# energy.net
KiCad netlist of a schematic drawn in Altium Designer
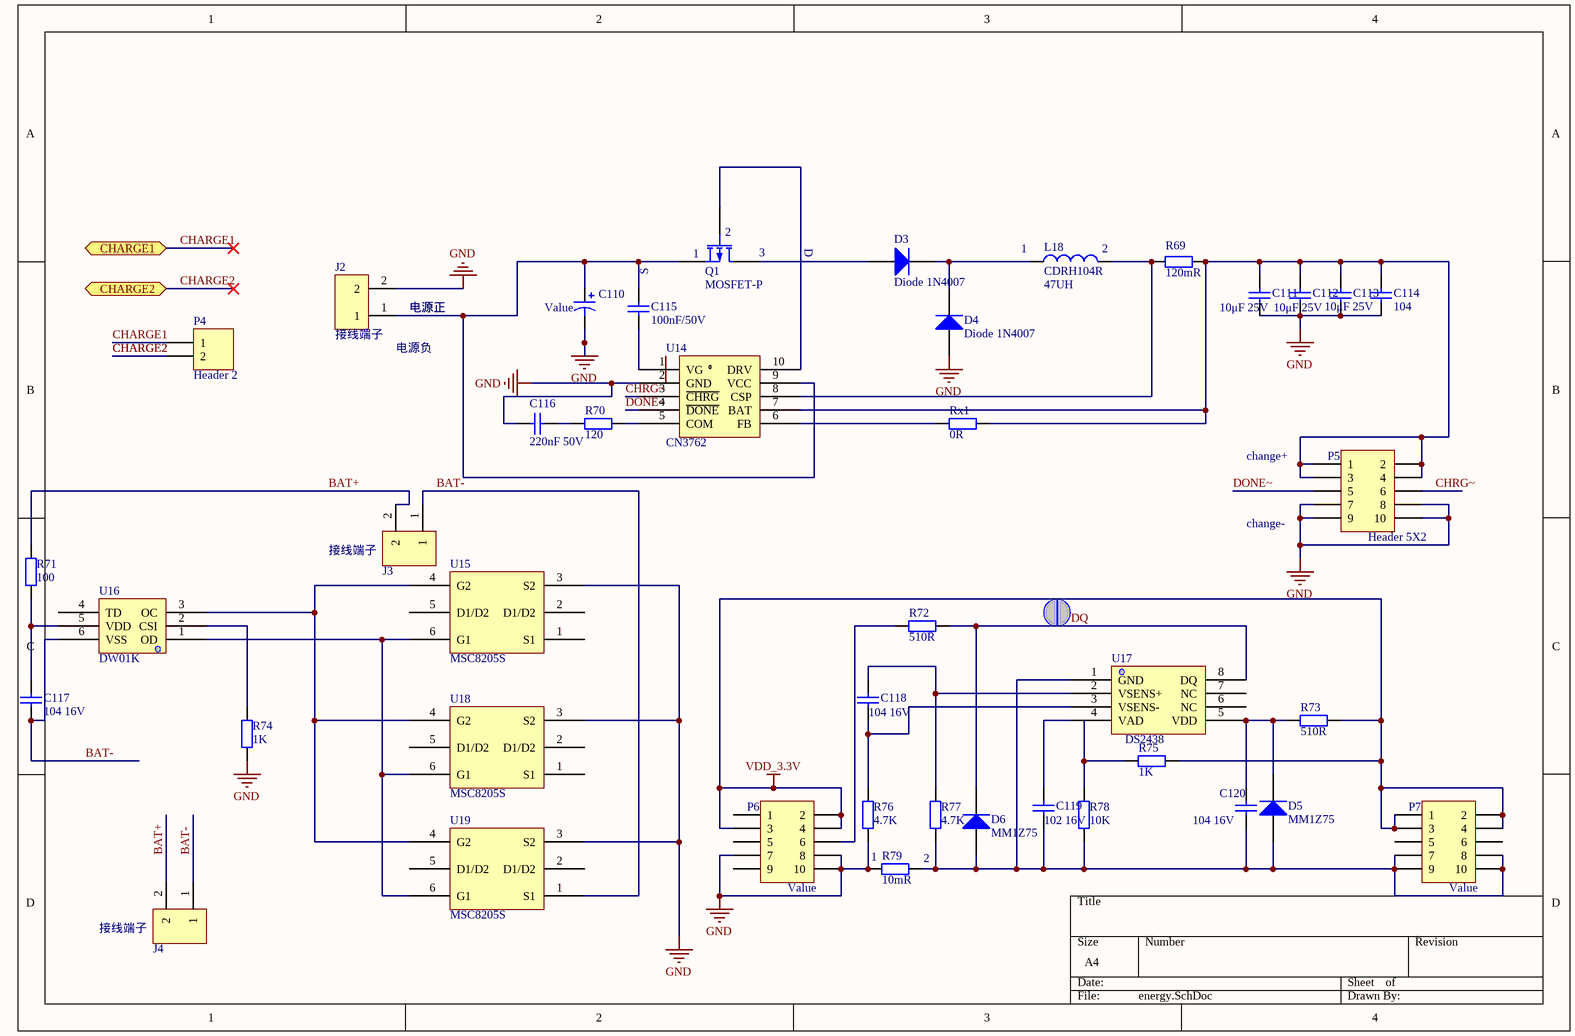
[diagram p0: energy.SchDoc]

(export (version "E")
  (design (tool "Eeschema 10.0.6"))
  (components
    (comp (ref "C110") (value "Value") (footprint "RB5.0-13") (libsource (lib "Spartan") (part "Cap_Pol")))
    (comp (ref "C111") (value "10μF 25V") (footprint "0805C") (libsource (lib "Spartan") (part "Cap")))
    (comp (ref "C112") (value "10μF 25V") (footprint "0805C") (libsource (lib "Spartan") (part "Cap")))
    (comp (ref "C113") (value "10μF 25V") (footprint "0805C") (libsource (lib "Spartan") (part "Cap")))
    (comp (ref "C114") (value "104") (footprint "0805C") (libsource (lib "Spartan") (part "Cap")))
    (comp (ref "C115") (value "100nF/50V") (footprint "0805C") (libsource (lib "Spartan") (part "Cap")))
    (comp (ref "C116") (value "220nF 50V") (footprint "0805C") (libsource (lib "Spartan") (part "Cap")))
    (comp (ref "C117") (value "104 16V") (footprint "0805C") (libsource (lib "PulsePower-Buck") (part "Cap")))
    (comp (ref "C118") (value "104 16V") (footprint "0805C") (libsource (lib "Spartan") (part "Cap")))
    (comp (ref "C119") (value "102 16V") (footprint "0805C") (libsource (lib "Spartan") (part "Cap")))
    (comp (ref "C120") (value "104 16V") (footprint "0805C") (libsource (lib "Spartan") (part "Cap")))
    (comp (ref "D3")
      (value "Diode 1N4007")
      (footprint "DO-41")
      (description "1 Amp General Purpose Rectifier")
      (fields (field (name "PUBLISHER") "Altium Limited"))
      (libsource (lib "Miscellaneous Devices") (part "Diode 1N4007"))
    )
    (comp (ref "D4")
      (value "Diode 1N4007")
      (footprint "DO-41")
      (description "1 Amp General Purpose Rectifier")
      (fields (field (name "PUBLISHER") "Altium Limited"))
      (libsource (lib "Miscellaneous Devices") (part "Diode 1N4007"))
    )
    (comp (ref "D5")
      (value "MM1Z75")
      (footprint "DO-41")
      (description "1 Amp General Purpose Rectifier")
      (fields (field (name "PUBLISHER") "Altium Limited"))
      (libsource (lib "Miscellaneous Devices") (part "Diode 1N4007"))
    )
    (comp (ref "D6")
      (value "MM1Z75")
      (footprint "DO-41")
      (description "1 Amp General Purpose Rectifier")
      (fields (field (name "PUBLISHER") "Altium Limited"))
      (libsource (lib "Miscellaneous Devices") (part "Diode 1N4007"))
    )
    (comp (ref "J2")
      (value "接线端子")
      (footprint "接线端子KF301-2P")
      (fields
        (field (name "原理图绘制者") "刘永钦")
        (field (name "原理图提供者") "刘永钦")
        (field (name "原理图审核人1") "徐鹏飞")
        (field (name "封装接线端子KF301-2P绘制者") "10级718学长")
        (field (name "封装接线端子KF301-2P提供者") "刘永钦")
        (field (name "封装接线端子KF301-2P审核人1") "徐鹏飞")
        (field (name "原理图审核人2") "朱觉文")
        (field (name "封装接线端子KF301-2P审核人2") "朱觉文")
      )
      (libsource (lib "") (part "接线端子_1"))
    )
    (comp (ref "J3")
      (value "接线端子")
      (footprint "接线端子KF301-2P")
      (fields
        (field (name "原理图绘制者") "刘永钦")
        (field (name "原理图提供者") "刘永钦")
        (field (name "原理图审核人1") "徐鹏飞")
        (field (name "封装接线端子KF301-2P绘制者") "10级718学长")
        (field (name "封装接线端子KF301-2P提供者") "刘永钦")
        (field (name "封装接线端子KF301-2P审核人1") "徐鹏飞")
        (field (name "原理图审核人2") "朱觉文")
        (field (name "封装接线端子KF301-2P审核人2") "朱觉文")
      )
      (libsource (lib "Dugu") (part "接线端子"))
    )
    (comp (ref "J4")
      (value "接线端子")
      (footprint "接线端子KF301-2P")
      (fields
        (field (name "原理图绘制者") "刘永钦")
        (field (name "原理图提供者") "刘永钦")
        (field (name "原理图审核人1") "徐鹏飞")
        (field (name "封装接线端子KF301-2P绘制者") "10级718学长")
        (field (name "封装接线端子KF301-2P提供者") "刘永钦")
        (field (name "封装接线端子KF301-2P审核人1") "徐鹏飞")
        (field (name "原理图审核人2") "朱觉文")
        (field (name "封装接线端子KF301-2P审核人2") "朱觉文")
      )
      (libsource (lib "Dugu") (part "接线端子"))
    )
    (comp (ref "L18")
      (value "CDRH104R")
      (footprint "0402-A")
      (description "Inductor")
      (fields (field (name "ALTIUM_VALUE") "47UH") (field (name "PUBLISHER") "Altium Limited"))
      (libsource (lib "Miscellaneous Devices") (part "Inductor"))
    )
    (comp (ref "P4")
      (value "Header 2")
      (footprint "HDR1X2")
      (description "Header, 2-Pin")
      (fields (field (name "PUBLISHER") "Altium Limited"))
      (libsource (lib "Miscellaneous Connectors") (part "Header 2"))
    )
    (comp (ref "P5")
      (value "Header 5X2")
      (footprint "HDR2X5")
      (description "Header, 5-Pin, Dual row")
      (fields (field (name "PUBLISHER") "Altium Limited"))
      (libsource (lib "Miscellaneous Connectors") (part "Header 5X2"))
    )
    (comp (ref "P6")
      (value "Value")
      (footprint "HDR2X5")
      (description "Header, 5-Pin, Dual row")
      (fields (field (name "PUBLISHER") "Altium Limited"))
      (libsource (lib "Miscellaneous Connectors") (part "Header 5X2"))
    )
    (comp (ref "P7")
      (value "Value")
      (footprint "HDR2X5")
      (description "Header, 5-Pin, Dual row")
      (fields (field (name "PUBLISHER") "Altium Limited"))
      (libsource (lib "Miscellaneous Connectors") (part "Header 5X2"))
    )
    (comp (ref "Q1")
      (value "MOSFET-P")
      (footprint "E3")
      (description "P-Channel MOSFET")
      (fields (field (name "PUBLISHER") "Altium Limited"))
      (libsource (lib "Miscellaneous Devices") (part "MOSFET-P"))
    )
    (comp (ref "R69") (value "120mR") (footprint "0805R") (libsource (lib "") (part "Res_2")))
    (comp (ref "R70") (value "120") (footprint "0805R") (libsource (lib "") (part "Res_2")))
    (comp (ref "R71") (value "100") (footprint "0805R") (libsource (lib "") (part "Res_1")))
    (comp (ref "R72") (value "510R") (footprint "0805R") (libsource (lib "") (part "Res_2")))
    (comp (ref "R73") (value "510R") (footprint "0805R") (libsource (lib "") (part "Res_2")))
    (comp (ref "R74") (value "1K") (footprint "0805R") (libsource (lib "") (part "Res_1")))
    (comp (ref "R75") (value "1K") (footprint "0805R") (libsource (lib "") (part "Res_2")))
    (comp (ref "R76") (value "4.7K") (footprint "0805R") (libsource (lib "") (part "Res_3")))
    (comp (ref "R77") (value "4.7K") (footprint "0805R") (libsource (lib "") (part "Res_3")))
    (comp (ref "R78") (value "10K") (footprint "0805R") (libsource (lib "") (part "Res_3")))
    (comp (ref "R79") (value "10mR") (footprint "0805R") (libsource (lib "Spartan") (part "Res")))
    (comp (ref "Rx1") (value "0R") (footprint "0805R") (libsource (lib "") (part "Res_2")))
    (comp (ref "U14")
      (value "CN3762")
      (footprint "SOP100P600X175-10N")
      (libsource (lib "EnergyChips") (part "CN3762"))
    )
    (comp (ref "U15")
      (value "MSC8205S")
      (footprint "SOT95P290X124-6N")
      (libsource (lib "EnergyChips") (part "MSC8205S"))
    )
    (comp (ref "U16")
      (value "DW01K")
      (footprint "SOT95P280X125-6N")
      (libsource (lib "EnergyChips") (part "DW01K"))
    )
    (comp (ref "U17")
      (value "DS2438")
      (footprint "SOP127P800X216-8N")
      (libsource (lib "EnergyChips") (part "DS2438"))
    )
    (comp (ref "U18")
      (value "MSC8205S")
      (footprint "SOT95P290X124-6N")
      (libsource (lib "EnergyChips") (part "MSC8205S"))
    )
    (comp (ref "U19")
      (value "MSC8205S")
      (footprint "SOT95P290X124-6N")
      (libsource (lib "EnergyChips") (part "MSC8205S"))
    )
  )
  (nets
    (net (code "1") (name "/BAT+") (class "Default")
      (node (ref "J3") (pin "2") (pinfunction "2_2") (pintype "power_in"))
      (node (ref "J4") (pin "2") (pinfunction "2_2") (pintype "power_in"))
      (node (ref "R71") (pin "2") (pinfunction "2_2") (pintype "passive"))
    )
    (net (code "2") (name "/BAT-") (class "Default")
      (node (ref "C117") (pin "1") (pinfunction "1_1") (pintype "passive"))
      (node (ref "J3") (pin "1") (pinfunction "1_1") (pintype "power_in"))
      (node (ref "J4") (pin "1") (pinfunction "1_1") (pintype "power_in"))
      (node (ref "U16") (pin "6") (pinfunction "VSS_6") (pintype "passive"))
      (node (ref "U19") (pin "1") (pinfunction "S1_1") (pintype "passive"))
    )
    (net (code "3") (name "/CHARGE1") (class "Default")
      (node (ref "P4") (pin "1") (pinfunction "1_1") (pintype "passive+no_connect"))
    )
    (net (code "4") (name "/CHARGE2") (class "Default")
      (node (ref "P4") (pin "2") (pinfunction "2_2") (pintype "passive+no_connect"))
    )
    (net (code "5") (name "/CHRG~") (class "Default")
      (node (ref "P5") (pin "6") (pinfunction "6_6") (pintype "passive"))
      (node (ref "U14") (pin "3") (pinfunction "~{CHRG}_3") (pintype "passive"))
    )
    (net (code "6") (name "/DONE~") (class "Default")
      (node (ref "P5") (pin "5") (pinfunction "5_5") (pintype "passive"))
      (node (ref "U14") (pin "4") (pinfunction "~{DONE}_4") (pintype "passive"))
    )
    (net (code "7") (name "/DQ") (class "Default")
      (node (ref "D6") (pin "2") (pinfunction "K_2") (pintype "passive"))
      (node (ref "R72") (pin "1") (pinfunction "1_1") (pintype "passive"))
      (node (ref "U17") (pin "8") (pinfunction "DQ_8") (pintype "passive"))
    )
    (net (code "8") (name "GND") (class "Default")
      (node (ref "C110") (pin "2") (pinfunction "2_2") (pintype "passive"))
      (node (ref "C111") (pin "2") (pinfunction "2_2") (pintype "passive"))
      (node (ref "C112") (pin "2") (pinfunction "2_2") (pintype "passive"))
      (node (ref "C113") (pin "2") (pinfunction "2_2") (pintype "passive"))
      (node (ref "C114") (pin "2") (pinfunction "2_2") (pintype "passive"))
      (node (ref "C116") (pin "2") (pinfunction "2_2") (pintype "passive"))
      (node (ref "D4") (pin "1") (pinfunction "A_1") (pintype "passive"))
      (node (ref "J2") (pin "2") (pinfunction "2_2") (pintype "power_in"))
      (node (ref "P5") (pin "10") (pinfunction "10_10") (pintype "passive"))
      (node (ref "P5") (pin "7") (pinfunction "7_7") (pintype "passive"))
      (node (ref "P5") (pin "8") (pinfunction "8_8") (pintype "passive"))
      (node (ref "P5") (pin "9") (pinfunction "9_9") (pintype "passive"))
      (node (ref "P6") (pin "10") (pinfunction "10_10") (pintype "passive"))
      (node (ref "P6") (pin "7") (pinfunction "7_7") (pintype "passive"))
      (node (ref "P6") (pin "8") (pinfunction "8_8") (pintype "passive"))
      (node (ref "R74") (pin "1") (pinfunction "1_1") (pintype "passive"))
      (node (ref "R76") (pin "2") (pinfunction "2_2") (pintype "passive"))
      (node (ref "R79") (pin "1") (pinfunction "1_1") (pintype "passive"))
      (node (ref "U14") (pin "2") (pinfunction "GND_2") (pintype "passive"))
      (node (ref "U15") (pin "3") (pinfunction "S2_3") (pintype "passive"))
      (node (ref "U18") (pin "3") (pinfunction "S2_3") (pintype "passive"))
      (node (ref "U19") (pin "3") (pinfunction "S2_3") (pintype "passive"))
    )
    (net (code "9") (name "Net-(C116-Pad1)") (class "Default")
      (node (ref "C116") (pin "1") (pinfunction "1_1") (pintype "passive"))
      (node (ref "R70") (pin "2") (pinfunction "2_2") (pintype "passive"))
    )
    (net (code "10") (name "Net-(D3-A)") (class "Default")
      (node (ref "D3") (pin "1") (pinfunction "A_1") (pintype "passive"))
      (node (ref "Q1") (pin "1") (pinfunction "D_1") (pintype "passive"))
    )
    (net (code "11") (name "Net-(D3-K)") (class "Default")
      (node (ref "D3") (pin "2") (pinfunction "K_2") (pintype "passive"))
      (node (ref "D4") (pin "2") (pinfunction "K_2") (pintype "passive"))
      (node (ref "L18") (pin "1") (pinfunction "1_1") (pintype "passive"))
    )
    (net (code "12") (name "Net-(D5-A)") (class "Default")
      (node (ref "C119") (pin "2") (pinfunction "2_2") (pintype "passive"))
      (node (ref "C120") (pin "2") (pinfunction "2_2") (pintype "passive"))
      (node (ref "D5") (pin "1") (pinfunction "A_1") (pintype "passive"))
      (node (ref "D6") (pin "1") (pinfunction "A_1") (pintype "passive"))
      (node (ref "P7") (pin "10") (pinfunction "10_10") (pintype "passive"))
      (node (ref "P7") (pin "7") (pinfunction "7_7") (pintype "passive"))
      (node (ref "P7") (pin "8") (pinfunction "8_8") (pintype "passive"))
      (node (ref "P7") (pin "9") (pinfunction "9_9") (pintype "passive"))
      (node (ref "R77") (pin "2") (pinfunction "2_2") (pintype "passive"))
      (node (ref "R78") (pin "2") (pinfunction "2_2") (pintype "passive"))
      (node (ref "R79") (pin "2") (pinfunction "2_2") (pintype "passive"))
      (node (ref "U17") (pin "1") (pinfunction "GND_1") (pintype "passive"))
    )
    (net (code "13") (name "Net-(D5-K)") (class "Default")
      (node (ref "C120") (pin "1") (pinfunction "1_1") (pintype "passive"))
      (node (ref "D5") (pin "2") (pinfunction "K_2") (pintype "passive"))
      (node (ref "R73") (pin "2") (pinfunction "2_2") (pintype "passive"))
      (node (ref "U17") (pin "5") (pinfunction "VDD_5") (pintype "passive"))
    )
    (net (code "14") (name "Net-(P6-Pad6)") (class "Default")
      (node (ref "P6") (pin "6") (pinfunction "6_6") (pintype "passive"))
      (node (ref "R72") (pin "2") (pinfunction "2_2") (pintype "passive"))
    )
    (net (code "15") (name "Net-(Q1-G)") (class "Default")
      (node (ref "Q1") (pin "2") (pinfunction "G_2") (pintype "passive"))
      (node (ref "U14") (pin "10") (pinfunction "DRV_10") (pintype "passive"))
    )
    (net (code "16") (name "Net-(Q1-S)") (class "Default")
      (node (ref "C110") (pin "1") (pinfunction "1_1") (pintype "passive"))
      (node (ref "C115") (pin "2") (pinfunction "2_2") (pintype "passive"))
      (node (ref "J2") (pin "1") (pinfunction "1_1") (pintype "power_in"))
      (node (ref "Q1") (pin "3") (pinfunction "S_3") (pintype "passive"))
      (node (ref "U14") (pin "9") (pinfunction "VCC_9") (pintype "passive"))
    )
    (net (code "17") (name "Net-(R75-Pad2)") (class "Default")
      (node (ref "R75") (pin "2") (pinfunction "2_2") (pintype "passive"))
      (node (ref "R78") (pin "1") (pinfunction "1_1") (pintype "passive"))
    )
    (net (code "18") (name "Net-(U14-BAT)") (class "Default")
      (node (ref "C111") (pin "1") (pinfunction "1_1") (pintype "passive"))
      (node (ref "C112") (pin "1") (pinfunction "1_1") (pintype "passive"))
      (node (ref "C113") (pin "1") (pinfunction "1_1") (pintype "passive"))
      (node (ref "C114") (pin "1") (pinfunction "1_1") (pintype "passive"))
      (node (ref "P5") (pin "1") (pinfunction "1_1") (pintype "passive"))
      (node (ref "P5") (pin "2") (pinfunction "2_2") (pintype "passive"))
      (node (ref "P5") (pin "3") (pinfunction "3_3") (pintype "passive"))
      (node (ref "P5") (pin "4") (pinfunction "4_4") (pintype "passive"))
      (node (ref "R69") (pin "1") (pinfunction "1_1") (pintype "passive"))
      (node (ref "Rx1") (pin "1") (pinfunction "1_1") (pintype "passive"))
      (node (ref "U14") (pin "7") (pinfunction "BAT_7") (pintype "passive"))
    )
    (net (code "19") (name "Net-(U14-COM)") (class "Default")
      (node (ref "R70") (pin "1") (pinfunction "1_1") (pintype "passive"))
      (node (ref "U14") (pin "5") (pinfunction "COM_5") (pintype "passive"))
    )
    (net (code "20") (name "Net-(U14-CSP)") (class "Default")
      (node (ref "L18") (pin "2") (pinfunction "2_2") (pintype "passive"))
      (node (ref "R69") (pin "2") (pinfunction "2_2") (pintype "passive"))
      (node (ref "U14") (pin "8") (pinfunction "CSP_8") (pintype "passive"))
    )
    (net (code "21") (name "Net-(U14-FB)") (class "Default")
      (node (ref "Rx1") (pin "2") (pinfunction "2_2") (pintype "passive"))
      (node (ref "U14") (pin "6") (pinfunction "FB_6") (pintype "passive"))
    )
    (net (code "22") (name "Net-(U14-VG)") (class "Default")
      (node (ref "C115") (pin "1") (pinfunction "1_1") (pintype "passive"))
      (node (ref "U14") (pin "1") (pinfunction "VG_1") (pintype "passive"))
    )
    (net (code "23") (name "Net-(U15-G1)") (class "Default")
      (node (ref "U15") (pin "6") (pinfunction "G1_6") (pintype "passive"))
      (node (ref "U16") (pin "1") (pinfunction "OD_1") (pintype "passive"))
      (node (ref "U18") (pin "6") (pinfunction "G1_6") (pintype "passive"))
      (node (ref "U19") (pin "6") (pinfunction "G1_6") (pintype "passive"))
    )
    (net (code "24") (name "Net-(U15-G2)") (class "Default")
      (node (ref "U15") (pin "4") (pinfunction "G2_4") (pintype "passive"))
      (node (ref "U16") (pin "3") (pinfunction "OC_3") (pintype "passive"))
      (node (ref "U18") (pin "4") (pinfunction "G2_4") (pintype "passive"))
      (node (ref "U19") (pin "4") (pinfunction "G2_4") (pintype "passive"))
    )
    (net (code "25") (name "Net-(U16-CSI)") (class "Default")
      (node (ref "R74") (pin "2") (pinfunction "2_2") (pintype "passive"))
      (node (ref "U16") (pin "2") (pinfunction "CSI_2") (pintype "passive"))
    )
    (net (code "26") (name "Net-(U16-VDD)") (class "Default")
      (node (ref "C117") (pin "2") (pinfunction "2_2") (pintype "passive"))
      (node (ref "R71") (pin "1") (pinfunction "1_1") (pintype "passive"))
      (node (ref "U16") (pin "5") (pinfunction "VDD_5") (pintype "passive"))
    )
    (net (code "27") (name "Net-(U17-VAD)") (class "Default")
      (node (ref "C119") (pin "1") (pinfunction "1_1") (pintype "passive"))
      (node (ref "U17") (pin "4") (pinfunction "VAD_4") (pintype "passive"))
    )
    (net (code "28") (name "Net-(U17-VSENS+)") (class "Default")
      (node (ref "C118") (pin "1") (pinfunction "1_1") (pintype "passive"))
      (node (ref "R77") (pin "1") (pinfunction "1_1") (pintype "passive"))
      (node (ref "U17") (pin "2") (pinfunction "VSENS+_2") (pintype "passive"))
    )
    (net (code "29") (name "Net-(U17-VSENS-)") (class "Default")
      (node (ref "C118") (pin "2") (pinfunction "2_2") (pintype "passive"))
      (node (ref "R76") (pin "1") (pinfunction "1_1") (pintype "passive"))
      (node (ref "U17") (pin "3") (pinfunction "VSENS-_3") (pintype "passive"))
    )
    (net (code "30") (name "VDD_3.3V") (class "Default")
      (node (ref "P6") (pin "2") (pinfunction "2_2") (pintype "passive"))
      (node (ref "P6") (pin "3") (pinfunction "3_3") (pintype "passive"))
      (node (ref "P6") (pin "4") (pinfunction "4_4") (pintype "passive"))
      (node (ref "P7") (pin "1") (pinfunction "1_1") (pintype "passive"))
      (node (ref "P7") (pin "2") (pinfunction "2_2") (pintype "passive"))
      (node (ref "P7") (pin "3") (pinfunction "3_3") (pintype "passive"))
      (node (ref "P7") (pin "4") (pinfunction "4_4") (pintype "passive"))
      (node (ref "R73") (pin "1") (pinfunction "1_1") (pintype "passive"))
      (node (ref "R75") (pin "1") (pinfunction "1_1") (pintype "passive"))
    )
    (net (code "31") (name "unconnected-(P6-Pad1)") (class "Default")
      (node (ref "P6") (pin "1") (pinfunction "1_1") (pintype "passive"))
    )
    (net (code "32") (name "unconnected-(P6-Pad5)") (class "Default")
      (node (ref "P6") (pin "5") (pinfunction "5_5") (pintype "passive"))
    )
    (net (code "33") (name "unconnected-(P6-Pad9)") (class "Default")
      (node (ref "P6") (pin "9") (pinfunction "9_9") (pintype "passive"))
    )
    (net (code "34") (name "unconnected-(P7-Pad5)") (class "Default")
      (node (ref "P7") (pin "5") (pinfunction "5_5") (pintype "passive"))
    )
    (net (code "35") (name "unconnected-(P7-Pad6)") (class "Default")
      (node (ref "P7") (pin "6") (pinfunction "6_6") (pintype "passive"))
    )
    (net (code "36") (name "unconnected-(U15-D1{slash}D2-Pad2)") (class "Default")
      (node (ref "U15") (pin "2") (pinfunction "D1/D2_2") (pintype "passive"))
    )
    (net (code "37") (name "unconnected-(U15-D1{slash}D2-Pad5)") (class "Default")
      (node (ref "U15") (pin "5") (pinfunction "D1/D2_5") (pintype "passive"))
    )
    (net (code "38") (name "unconnected-(U15-S1-Pad1)") (class "Default")
      (node (ref "U15") (pin "1") (pinfunction "S1_1") (pintype "passive"))
    )
    (net (code "39") (name "unconnected-(U16-TD-Pad4)") (class "Default")
      (node (ref "U16") (pin "4") (pinfunction "TD_4") (pintype "passive"))
    )
    (net (code "40") (name "unconnected-(U17-NC-Pad6)") (class "Default")
      (node (ref "U17") (pin "6") (pinfunction "NC_6") (pintype "passive"))
    )
    (net (code "41") (name "unconnected-(U17-NC-Pad7)") (class "Default")
      (node (ref "U17") (pin "7") (pinfunction "NC_7") (pintype "passive"))
    )
    (net (code "42") (name "unconnected-(U18-D1{slash}D2-Pad2)") (class "Default")
      (node (ref "U18") (pin "2") (pinfunction "D1/D2_2") (pintype "passive"))
    )
    (net (code "43") (name "unconnected-(U18-D1{slash}D2-Pad5)") (class "Default")
      (node (ref "U18") (pin "5") (pinfunction "D1/D2_5") (pintype "passive"))
    )
    (net (code "44") (name "unconnected-(U18-S1-Pad1)") (class "Default")
      (node (ref "U18") (pin "1") (pinfunction "S1_1") (pintype "passive"))
    )
    (net (code "45") (name "unconnected-(U19-D1{slash}D2-Pad2)") (class "Default")
      (node (ref "U19") (pin "2") (pinfunction "D1/D2_2") (pintype "passive"))
    )
    (net (code "46") (name "unconnected-(U19-D1{slash}D2-Pad5)") (class "Default")
      (node (ref "U19") (pin "5") (pinfunction "D1/D2_5") (pintype "passive"))
    )
  )
)
